# TLV751_PINOUT.net
KiCad netlist of a schematic drawn in Altium Designer
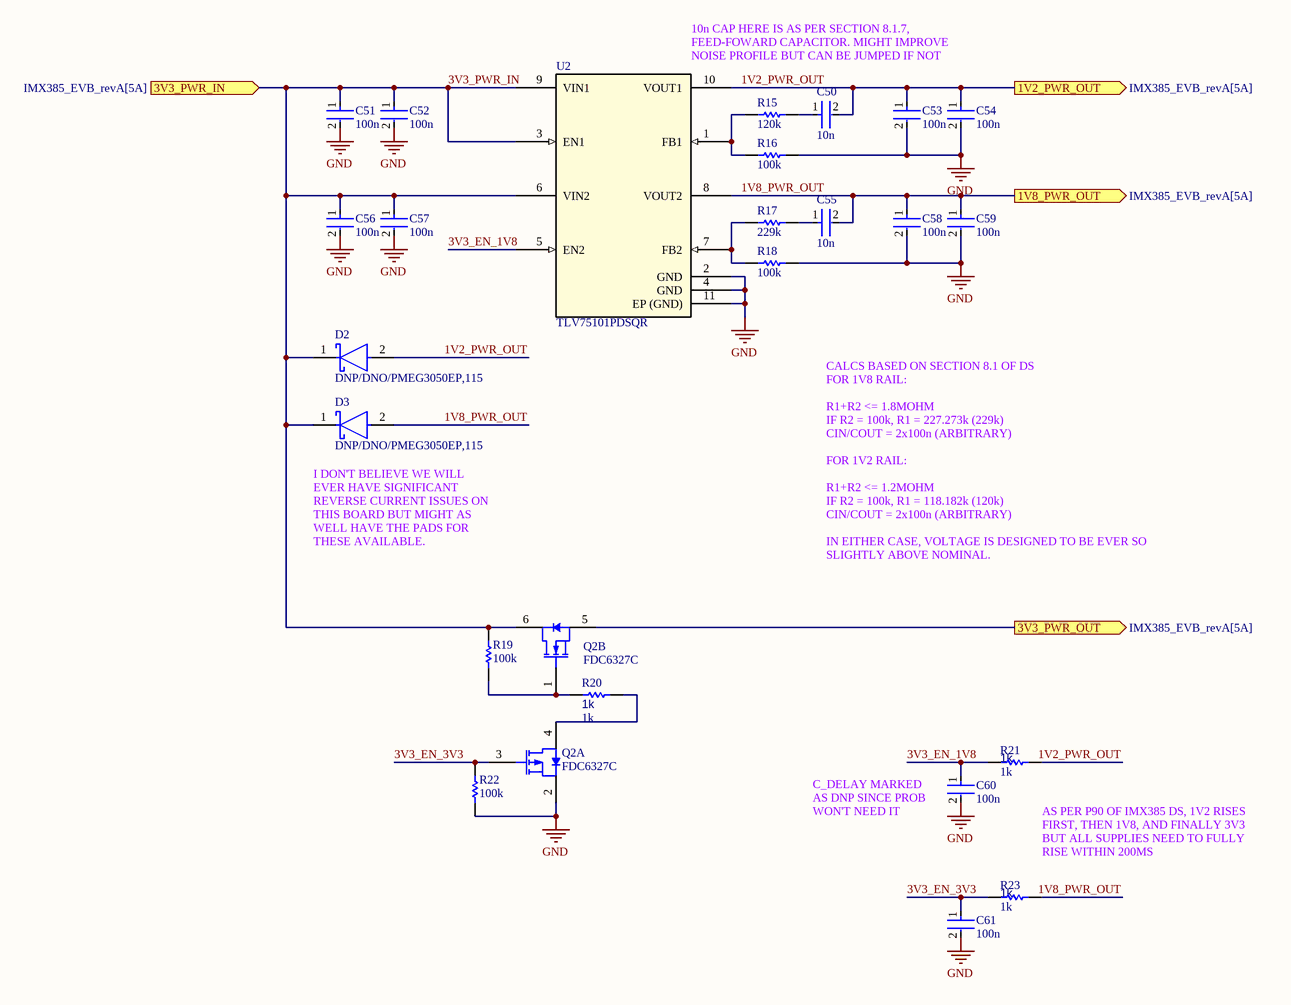
[diagram p0: TLV751_PINOUT.SchDoc]

(export (version "E")
  (design (tool "Eeschema 10.0.6"))
  (components
    (comp (ref "C50")
      (value "10n")
      (footprint "FP-0402-L_1_0_0_05-W_0_5-IPC_A")
      (description "LARGE PADS, 0402 CAP, CHANGE COMMENT TO MATCH REAL P/N")
      (libsource (lib "Space Concordia") (part "b4654b650e69147ec39a6b967a45e02"))
    )
    (comp (ref "C51")
      (value "100n")
      (footprint "FP-0402-L_1_0_0_05-W_0_5-IPC_A")
      (description "LARGE PADS, 0402 CAP, CHANGE COMMENT TO MATCH REAL P/N")
      (libsource (lib "Space Concordia") (part "b4654b650e69147ec39a6b967a45e02"))
    )
    (comp (ref "C52")
      (value "100n")
      (footprint "FP-0402-L_1_0_0_05-W_0_5-IPC_A")
      (description "LARGE PADS, 0402 CAP, CHANGE COMMENT TO MATCH REAL P/N")
      (libsource (lib "Space Concordia") (part "b4654b650e69147ec39a6b967a45e02"))
    )
    (comp (ref "C53")
      (value "100n")
      (footprint "FP-0402-L_1_0_0_05-W_0_5-IPC_A")
      (description "LARGE PADS, 0402 CAP, CHANGE COMMENT TO MATCH REAL P/N")
      (libsource (lib "Space Concordia") (part "b4654b650e69147ec39a6b967a45e02"))
    )
    (comp (ref "C54")
      (value "100n")
      (footprint "FP-0402-L_1_0_0_05-W_0_5-IPC_A")
      (description "LARGE PADS, 0402 CAP, CHANGE COMMENT TO MATCH REAL P/N")
      (libsource (lib "Space Concordia") (part "b4654b650e69147ec39a6b967a45e02"))
    )
    (comp (ref "C55")
      (value "10n")
      (footprint "FP-0402-L_1_0_0_05-W_0_5-IPC_A")
      (description "LARGE PADS, 0402 CAP, CHANGE COMMENT TO MATCH REAL P/N")
      (libsource (lib "Space Concordia") (part "b4654b650e69147ec39a6b967a45e02"))
    )
    (comp (ref "C56")
      (value "100n")
      (footprint "FP-0402-L_1_0_0_05-W_0_5-IPC_A")
      (description "LARGE PADS, 0402 CAP, CHANGE COMMENT TO MATCH REAL P/N")
      (libsource (lib "Space Concordia") (part "b4654b650e69147ec39a6b967a45e02"))
    )
    (comp (ref "C57")
      (value "100n")
      (footprint "FP-0402-L_1_0_0_05-W_0_5-IPC_A")
      (description "LARGE PADS, 0402 CAP, CHANGE COMMENT TO MATCH REAL P/N")
      (libsource (lib "Space Concordia") (part "b4654b650e69147ec39a6b967a45e02"))
    )
    (comp (ref "C58")
      (value "100n")
      (footprint "FP-0402-L_1_0_0_05-W_0_5-IPC_A")
      (description "LARGE PADS, 0402 CAP, CHANGE COMMENT TO MATCH REAL P/N")
      (libsource (lib "Space Concordia") (part "b4654b650e69147ec39a6b967a45e02"))
    )
    (comp (ref "C59")
      (value "100n")
      (footprint "FP-0402-L_1_0_0_05-W_0_5-IPC_A")
      (description "LARGE PADS, 0402 CAP, CHANGE COMMENT TO MATCH REAL P/N")
      (libsource (lib "Space Concordia") (part "b4654b650e69147ec39a6b967a45e02"))
    )
    (comp (ref "C60")
      (value "100n")
      (footprint "FP-0402-L_1_0_0_05-W_0_5-IPC_A")
      (description "LARGE PADS, 0402 CAP, CHANGE COMMENT TO MATCH REAL P/N")
      (libsource (lib "Space Concordia") (part "b4654b650e69147ec39a6b967a45e02"))
    )
    (comp (ref "C61")
      (value "100n")
      (footprint "FP-0402-L_1_0_0_05-W_0_5-IPC_A")
      (description "LARGE PADS, 0402 CAP, CHANGE COMMENT TO MATCH REAL P/N")
      (libsource (lib "Space Concordia") (part "b4654b650e69147ec39a6b967a45e02"))
    )
    (comp (ref "D2")
      (value "DNP/DNO/PMEG3050EP,115")
      (footprint "FP-SOD128-MFG")
      (description "DIODE SCHOTTKY 30V 5A SOD128")
      (libsource (lib "Altium Content Vault") (part "1d6ec82d83fb6aee721767c19dac4b9"))
    )
    (comp (ref "D3")
      (value "DNP/DNO/PMEG3050EP,115")
      (footprint "FP-SOD128-MFG")
      (description "DIODE SCHOTTKY 30V 5A SOD128")
      (libsource (lib "Altium Content Vault") (part "1d6ec82d83fb6aee721767c19dac4b9"))
    )
    (comp (ref "Q2")
      (value "FDC6327C")
      (footprint "FAIR-SOT23-6_V")
      (fields (field (name "MANUFACTURER") "Fairchild"))
      (libsource (lib "Altium Content Vault") (part "PEMOS-SGD-NEMOS-GSD-6"))
    )
    (comp (ref "R15")
      (value "120k")
      (footprint "R0603B")
      (description "Resistor")
      (libsource (lib "Space Concordia") (part "Resistor"))
    )
    (comp (ref "R16")
      (value "100k")
      (footprint "R0603B")
      (description "Resistor")
      (libsource (lib "Space Concordia") (part "Resistor"))
    )
    (comp (ref "R17")
      (value "229k")
      (footprint "R0603B")
      (description "Resistor")
      (libsource (lib "Space Concordia") (part "Resistor"))
    )
    (comp (ref "R18")
      (value "100k")
      (footprint "R0603B")
      (description "Resistor")
      (libsource (lib "Space Concordia") (part "Resistor"))
    )
    (comp (ref "R19")
      (value "100k")
      (footprint "R0603B")
      (description "Resistor")
      (libsource (lib "Space Concordia") (part "Resistor"))
    )
    (comp (ref "R20")
      (value "1k")
      (footprint "R0603B")
      (description "Resistor")
      (fields (field (name "ALTIUM_VALUE") "1k"))
      (libsource (lib "Space Concordia") (part "Resistor"))
    )
    (comp (ref "R21")
      (value "1k")
      (footprint "R0603B")
      (description "Resistor")
      (fields (field (name "ALTIUM_VALUE") "1k"))
      (libsource (lib "Space Concordia") (part "Resistor"))
    )
    (comp (ref "R22")
      (value "100k")
      (footprint "R0603B")
      (description "Resistor")
      (libsource (lib "Space Concordia") (part "Resistor"))
    )
    (comp (ref "R23")
      (value "1k")
      (footprint "R0603B")
      (description "Resistor")
      (fields (field (name "ALTIUM_VALUE") "1k"))
      (libsource (lib "Space Concordia") (part "Resistor"))
    )
    (comp (ref "U2")
      (value "TLV75101PDSQR")
      (footprint "TLV75101PDSQR-Footprint-1")
      (description "500-mA, low-IQ, high-PSRR, dual-channel low-dropout (LDO) voltage regulator 10-WSON -40 to 125")
      (libsource (lib "Space Concordia") (part "TLV75101PDSQR"))
    )
  )
  (nets
    (net (code "1") (name "/1V2_PWR_OUT") (class "Default")
      (node (ref "C50") (pin "2") (pinfunction "2_2") (pintype "passive"))
      (node (ref "C53") (pin "1") (pinfunction "1_1") (pintype "passive"))
      (node (ref "C54") (pin "1") (pinfunction "1_1") (pintype "passive"))
      (node (ref "D2") (pin "2") (pinfunction "A_2") (pintype "passive"))
      (node (ref "R21") (pin "1") (pinfunction "1_1") (pintype "passive"))
      (node (ref "U2") (pin "10") (pinfunction "VOUT1_10") (pintype "power_in"))
    )
    (net (code "2") (name "/1V8_PWR_OUT") (class "Default")
      (node (ref "C55") (pin "2") (pinfunction "2_2") (pintype "passive"))
      (node (ref "C58") (pin "1") (pinfunction "1_1") (pintype "passive"))
      (node (ref "C59") (pin "1") (pinfunction "1_1") (pintype "passive"))
      (node (ref "D3") (pin "2") (pinfunction "A_2") (pintype "passive"))
      (node (ref "R23") (pin "1") (pinfunction "1_1") (pintype "passive"))
      (node (ref "U2") (pin "8") (pinfunction "VOUT2_8") (pintype "power_in"))
    )
    (net (code "3") (name "/3V3_EN_1V8") (class "Default")
      (node (ref "C60") (pin "1") (pinfunction "1_1") (pintype "passive"))
      (node (ref "R21") (pin "2") (pinfunction "2_2") (pintype "passive"))
      (node (ref "U2") (pin "5") (pinfunction "EN2_5") (pintype "input"))
    )
    (net (code "4") (name "/3V3_EN_3V3") (class "Default")
      (node (ref "C61") (pin "1") (pinfunction "1_1") (pintype "passive"))
      (node (ref "Q2") (pin "3") (pinfunction "G_3") (pintype "passive"))
      (node (ref "R22") (pin "1") (pinfunction "1_1") (pintype "passive"))
      (node (ref "R23") (pin "2") (pinfunction "2_2") (pintype "passive"))
    )
    (net (code "5") (name "/3V3_PWR_IN") (class "Default")
      (node (ref "C51") (pin "1") (pinfunction "1_1") (pintype "passive"))
      (node (ref "C52") (pin "1") (pinfunction "1_1") (pintype "passive"))
      (node (ref "C56") (pin "1") (pinfunction "1_1") (pintype "passive"))
      (node (ref "C57") (pin "1") (pinfunction "1_1") (pintype "passive"))
      (node (ref "D2") (pin "1") (pinfunction "C_1") (pintype "passive"))
      (node (ref "D3") (pin "1") (pinfunction "C_1") (pintype "passive"))
      (node (ref "Q2") (pin "6") (pinfunction "D_6") (pintype "passive"))
      (node (ref "R19") (pin "1") (pinfunction "1_1") (pintype "passive"))
      (node (ref "U2") (pin "3") (pinfunction "EN1_3") (pintype "input"))
      (node (ref "U2") (pin "6") (pinfunction "VIN2_6") (pintype "power_in"))
      (node (ref "U2") (pin "9") (pinfunction "VIN1_9") (pintype "power_in"))
    )
    (net (code "6") (name "/3V3_PWR_OUT") (class "Default")
      (node (ref "Q2") (pin "5") (pinfunction "S_5") (pintype "passive"))
    )
    (net (code "7") (name "GND") (class "Default")
      (node (ref "C51") (pin "2") (pinfunction "2_2") (pintype "passive"))
      (node (ref "C52") (pin "2") (pinfunction "2_2") (pintype "passive"))
      (node (ref "C53") (pin "2") (pinfunction "2_2") (pintype "passive"))
      (node (ref "C54") (pin "2") (pinfunction "2_2") (pintype "passive"))
      (node (ref "C56") (pin "2") (pinfunction "2_2") (pintype "passive"))
      (node (ref "C57") (pin "2") (pinfunction "2_2") (pintype "passive"))
      (node (ref "C58") (pin "2") (pinfunction "2_2") (pintype "passive"))
      (node (ref "C59") (pin "2") (pinfunction "2_2") (pintype "passive"))
      (node (ref "C60") (pin "2") (pinfunction "2_2") (pintype "passive"))
      (node (ref "C61") (pin "2") (pinfunction "2_2") (pintype "passive"))
      (node (ref "Q2") (pin "2") (pinfunction "S_2") (pintype "passive"))
      (node (ref "R16") (pin "1") (pinfunction "1_1") (pintype "passive"))
      (node (ref "R18") (pin "1") (pinfunction "1_1") (pintype "passive"))
      (node (ref "R22") (pin "2") (pinfunction "2_2") (pintype "passive"))
      (node (ref "U2") (pin "11") (pinfunction "EP_(GND)_11") (pintype "power_in"))
      (node (ref "U2") (pin "2") (pinfunction "GND_2") (pintype "power_in"))
      (node (ref "U2") (pin "4") (pinfunction "GND_4") (pintype "power_in"))
    )
    (net (code "8") (name "Net-(C50-Pad1)") (class "Default")
      (node (ref "C50") (pin "1") (pinfunction "1_1") (pintype "passive"))
      (node (ref "R15") (pin "1") (pinfunction "1_1") (pintype "passive"))
    )
    (net (code "9") (name "Net-(C55-Pad1)") (class "Default")
      (node (ref "C55") (pin "1") (pinfunction "1_1") (pintype "passive"))
      (node (ref "R17") (pin "1") (pinfunction "1_1") (pintype "passive"))
    )
    (net (code "10") (name "Net-(Q2A-D)") (class "Default")
      (node (ref "Q2") (pin "4") (pinfunction "D_4") (pintype "passive"))
      (node (ref "R20") (pin "2") (pinfunction "2_2") (pintype "passive"))
    )
    (net (code "11") (name "Net-(Q2B-G)") (class "Default")
      (node (ref "Q2") (pin "1") (pinfunction "G_1") (pintype "passive"))
      (node (ref "R19") (pin "2") (pinfunction "2_2") (pintype "passive"))
      (node (ref "R20") (pin "1") (pinfunction "1_1") (pintype "passive"))
    )
    (net (code "12") (name "Net-(U2-FB1)") (class "Default")
      (node (ref "R15") (pin "2") (pinfunction "2_2") (pintype "passive"))
      (node (ref "R16") (pin "2") (pinfunction "2_2") (pintype "passive"))
      (node (ref "U2") (pin "1") (pinfunction "FB1_1") (pintype "input"))
    )
    (net (code "13") (name "Net-(U2-FB2)") (class "Default")
      (node (ref "R17") (pin "2") (pinfunction "2_2") (pintype "passive"))
      (node (ref "R18") (pin "2") (pinfunction "2_2") (pintype "passive"))
      (node (ref "U2") (pin "7") (pinfunction "FB2_7") (pintype "input"))
    )
  )
)
